# brick_serial_ble_MDBT40.net
KiCad netlist of a schematic drawn in EAGLE
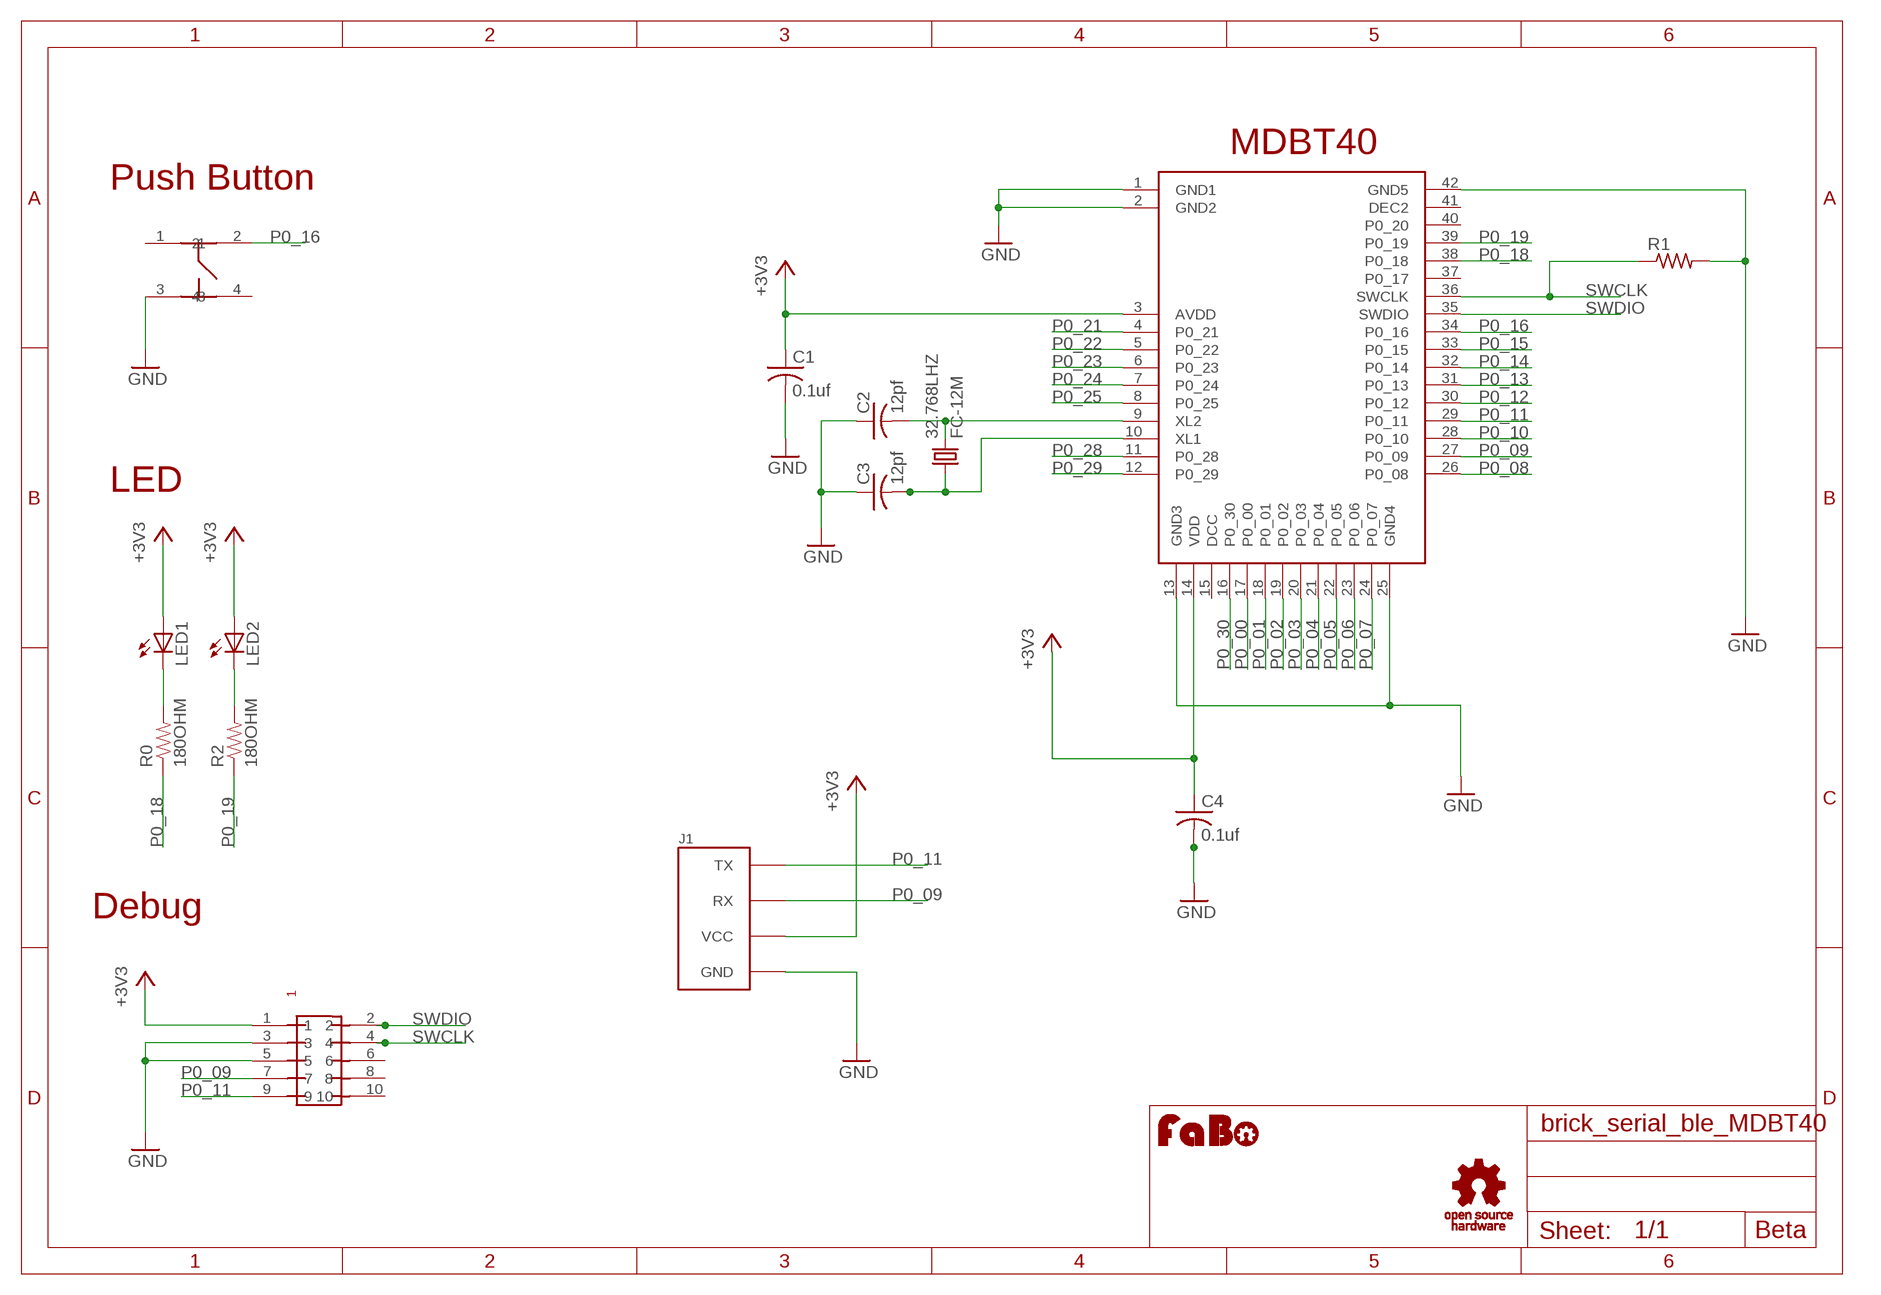
[diagram p0: schematic, sheet 1]

(export (version "E")
  (design (tool "Eeschema 10.0.6"))
  (components
    (comp (ref "32.768LHZ")
      (value "FC-12M")
      (footprint "eagle-import:FC-12M")
      (libsource (lib "eagle-import") (part "FC-12M"))
    )
    (comp (ref "C1")
      (value "0.1uf")
      (footprint "eagle-import:C0603")
      (libsource (lib "eagle-import") (part "C-USC0603"))
    )
    (comp (ref "C2")
      (value "12pf")
      (footprint "eagle-import:C0603")
      (libsource (lib "eagle-import") (part "C-USC0603"))
    )
    (comp (ref "C3")
      (value "12pf")
      (footprint "eagle-import:C0603")
      (libsource (lib "eagle-import") (part "C-USC0603"))
    )
    (comp (ref "C4")
      (value "0.1uf")
      (footprint "eagle-import:C0603")
      (libsource (lib "eagle-import") (part "C-USC0603"))
    )
    (comp (ref "J1")
      (value "BRICK_SERIAL")
      (footprint "eagle-import:BRICK_SERIAL")
      (libsource (lib "eagle-import") (part "BRICK_SERIAL"))
    )
    (comp (ref "LED1")
      (value "LEDCHIP-LED0603")
      (footprint "eagle-import:CHIP-LED0603")
      (libsource (lib "eagle-import") (part "LEDCHIP-LED0603"))
    )
    (comp (ref "LED2")
      (value "LEDCHIP-LED0603")
      (footprint "eagle-import:CHIP-LED0603")
      (libsource (lib "eagle-import") (part "LEDCHIP-LED0603"))
    )
    (comp (ref "R0")
      (value "180OHM")
      (footprint "eagle-import:0603-RES")
      (libsource (lib "eagle-import") (part "RESISTOR0603-RES"))
    )
    (comp (ref "R1")
      (value "R-US_R0603")
      (footprint "eagle-import:R0603")
      (libsource (lib "eagle-import") (part "R-US_R0603"))
    )
    (comp (ref "R2")
      (value "180OHM")
      (footprint "eagle-import:0603-RES")
      (libsource (lib "eagle-import") (part "RESISTOR0603-RES"))
    )
    (comp (ref "U$1")
      (value "RAYTAC-MDBT40")
      (footprint "eagle-import:RAYTAC-MDBT40")
      (libsource (lib "eagle-import") (part "RAYTAC-MDBT40"))
    )
    (comp (ref "U$2")
      (value "PIN-HEADER-SMT(1.27MM)2X5")
      (footprint "eagle-import:PIN-HEADER-SMT(1.27MM)2X5")
      (libsource (lib "eagle-import") (part "PIN-HEADER-SMT(1.27MM)2X5"))
    )
    (comp (ref "U$3")
      (value "LOGO_FABO-S")
      (footprint "eagle-import:LOGO_FABO_S")
      (libsource (lib "eagle-import") (part "LOGO_FABO-S"))
    )
    (comp (ref "U$4")
      (value "LOGO_OSHW_T-S")
      (footprint "eagle-import:LOGO_OSHW_T_S")
      (libsource (lib "eagle-import") (part "LOGO_OSHW_T-S"))
    )
    (comp (ref "U$5")
      (value "SWICTH-4P(KMR2)")
      (footprint "eagle-import:SWITCH-4P(KMR2)")
      (libsource (lib "eagle-import") (part "SWICTH-4P(KMR2)"))
    )
  )
  (nets
    (net (code "1") (name "+3V3") (class "Default")
      (node (ref "C1") (pin "1") (pinfunction "1_1") (pintype "passive"))
      (node (ref "C4") (pin "1") (pinfunction "1_1") (pintype "passive"))
      (node (ref "J1") (pin "VCC") (pinfunction "VCC_VCC") (pintype "bidirectional"))
      (node (ref "LED1") (pin "A") (pinfunction "A_A") (pintype "passive"))
      (node (ref "LED2") (pin "A") (pinfunction "A_A") (pintype "passive"))
      (node (ref "U$1") (pin "14") (pinfunction "VDD_14") (pintype "bidirectional"))
      (node (ref "U$1") (pin "3") (pinfunction "AVDD_3") (pintype "bidirectional"))
      (node (ref "U$2") (pin "1") (pinfunction "1_1") (pintype "bidirectional"))
    )
    (net (code "2") (name "/P0_00") (class "Default")
      (node (ref "U$1") (pin "17") (pinfunction "P0_00_17") (pintype "bidirectional"))
    )
    (net (code "3") (name "/P0_01") (class "Default")
      (node (ref "U$1") (pin "18") (pinfunction "P0_01_18") (pintype "bidirectional"))
    )
    (net (code "4") (name "/P0_02") (class "Default")
      (node (ref "U$1") (pin "19") (pinfunction "P0_02_19") (pintype "bidirectional"))
    )
    (net (code "5") (name "/P0_03") (class "Default")
      (node (ref "U$1") (pin "20") (pinfunction "P0_03_20") (pintype "bidirectional"))
    )
    (net (code "6") (name "/P0_04") (class "Default")
      (node (ref "U$1") (pin "21") (pinfunction "P0_04_21") (pintype "bidirectional"))
    )
    (net (code "7") (name "/P0_05") (class "Default")
      (node (ref "U$1") (pin "22") (pinfunction "P0_05_22") (pintype "bidirectional"))
    )
    (net (code "8") (name "/P0_06") (class "Default")
      (node (ref "U$1") (pin "23") (pinfunction "P0_06_23") (pintype "bidirectional"))
    )
    (net (code "9") (name "/P0_07") (class "Default")
      (node (ref "U$1") (pin "24") (pinfunction "P0_07_24") (pintype "bidirectional"))
    )
    (net (code "10") (name "/P0_08") (class "Default")
      (node (ref "U$1") (pin "26") (pinfunction "P0_08_26") (pintype "bidirectional"))
    )
    (net (code "11") (name "/P0_09") (class "Default")
      (node (ref "J1") (pin "RX") (pinfunction "RX_RX") (pintype "bidirectional"))
      (node (ref "U$1") (pin "27") (pinfunction "P0_09_27") (pintype "bidirectional"))
      (node (ref "U$2") (pin "7") (pinfunction "7_7") (pintype "bidirectional"))
    )
    (net (code "12") (name "/P0_10") (class "Default")
      (node (ref "U$1") (pin "28") (pinfunction "P0_10_28") (pintype "bidirectional"))
    )
    (net (code "13") (name "/P0_11") (class "Default")
      (node (ref "J1") (pin "TX") (pinfunction "TX_TX") (pintype "bidirectional"))
      (node (ref "U$1") (pin "29") (pinfunction "P0_11_29") (pintype "bidirectional"))
      (node (ref "U$2") (pin "9") (pinfunction "9_9") (pintype "bidirectional"))
    )
    (net (code "14") (name "/P0_12") (class "Default")
      (node (ref "U$1") (pin "30") (pinfunction "P0_12_30") (pintype "bidirectional"))
    )
    (net (code "15") (name "/P0_13") (class "Default")
      (node (ref "U$1") (pin "31") (pinfunction "P0_13_31") (pintype "bidirectional"))
    )
    (net (code "16") (name "/P0_14") (class "Default")
      (node (ref "U$1") (pin "32") (pinfunction "P0_14_32") (pintype "bidirectional"))
    )
    (net (code "17") (name "/P0_15") (class "Default")
      (node (ref "U$1") (pin "33") (pinfunction "P0_15_33") (pintype "bidirectional"))
    )
    (net (code "18") (name "/P0_16") (class "Default")
      (node (ref "U$1") (pin "34") (pinfunction "P0_16_34") (pintype "bidirectional"))
      (node (ref "U$5") (pin "2") (pinfunction "2_2") (pintype "bidirectional"))
    )
    (net (code "19") (name "/P0_18") (class "Default")
      (node (ref "R0") (pin "1") (pinfunction "1_1") (pintype "passive"))
      (node (ref "U$1") (pin "38") (pinfunction "P0_18_38") (pintype "bidirectional"))
    )
    (net (code "20") (name "/P0_19") (class "Default")
      (node (ref "R2") (pin "1") (pinfunction "1_1") (pintype "passive"))
      (node (ref "U$1") (pin "39") (pinfunction "P0_19_39") (pintype "bidirectional"))
    )
    (net (code "21") (name "/P0_21") (class "Default")
      (node (ref "U$1") (pin "4") (pinfunction "P0_21_4") (pintype "bidirectional"))
    )
    (net (code "22") (name "/P0_22") (class "Default")
      (node (ref "U$1") (pin "5") (pinfunction "P0_22_5") (pintype "bidirectional"))
    )
    (net (code "23") (name "/P0_23") (class "Default")
      (node (ref "U$1") (pin "6") (pinfunction "P0_23_6") (pintype "bidirectional"))
    )
    (net (code "24") (name "/P0_24") (class "Default")
      (node (ref "U$1") (pin "7") (pinfunction "P0_24_7") (pintype "bidirectional"))
    )
    (net (code "25") (name "/P0_25") (class "Default")
      (node (ref "U$1") (pin "8") (pinfunction "P0_25_8") (pintype "bidirectional"))
    )
    (net (code "26") (name "/P0_28") (class "Default")
      (node (ref "U$1") (pin "11") (pinfunction "P0_28_11") (pintype "bidirectional"))
    )
    (net (code "27") (name "/P0_29") (class "Default")
      (node (ref "U$1") (pin "12") (pinfunction "P0_29_12") (pintype "bidirectional"))
    )
    (net (code "28") (name "/P0_30") (class "Default")
      (node (ref "U$1") (pin "16") (pinfunction "P0_30_16") (pintype "bidirectional"))
    )
    (net (code "29") (name "/SWCLK") (class "Default")
      (node (ref "R1") (pin "1") (pinfunction "1_1") (pintype "passive"))
      (node (ref "U$1") (pin "36") (pinfunction "SWCLK_36") (pintype "bidirectional"))
      (node (ref "U$2") (pin "4") (pinfunction "4_4") (pintype "bidirectional"))
    )
    (net (code "30") (name "/SWDIO") (class "Default")
      (node (ref "U$1") (pin "35") (pinfunction "SWDIO_35") (pintype "bidirectional"))
      (node (ref "U$2") (pin "2") (pinfunction "2_2") (pintype "bidirectional"))
    )
    (net (code "31") (name "GND") (class "Default")
      (node (ref "C1") (pin "2") (pinfunction "2_2") (pintype "passive"))
      (node (ref "C2") (pin "1") (pinfunction "1_1") (pintype "passive"))
      (node (ref "C3") (pin "1") (pinfunction "1_1") (pintype "passive"))
      (node (ref "C4") (pin "2") (pinfunction "2_2") (pintype "passive"))
      (node (ref "J1") (pin "GND") (pinfunction "GND_GND") (pintype "bidirectional"))
      (node (ref "R1") (pin "2") (pinfunction "2_2") (pintype "passive"))
      (node (ref "U$1") (pin "1") (pinfunction "GND1_1") (pintype "bidirectional"))
      (node (ref "U$1") (pin "13") (pinfunction "GND3_13") (pintype "bidirectional"))
      (node (ref "U$1") (pin "2") (pinfunction "GND2_2") (pintype "bidirectional"))
      (node (ref "U$1") (pin "25") (pinfunction "GND4_25") (pintype "bidirectional"))
      (node (ref "U$1") (pin "42") (pinfunction "GND5_42") (pintype "bidirectional"))
      (node (ref "U$2") (pin "3") (pinfunction "3_3") (pintype "bidirectional"))
      (node (ref "U$2") (pin "5") (pinfunction "5_5") (pintype "bidirectional"))
      (node (ref "U$5") (pin "3") (pinfunction "3_3") (pintype "bidirectional"))
    )
    (net (code "32") (name "Net-(LED1-PadC)") (class "Default")
      (node (ref "LED1") (pin "C") (pinfunction "C_C") (pintype "passive"))
      (node (ref "R0") (pin "2") (pinfunction "2_2") (pintype "passive"))
    )
    (net (code "33") (name "Net-(LED2-PadC)") (class "Default")
      (node (ref "LED2") (pin "C") (pinfunction "C_C") (pintype "passive"))
      (node (ref "R2") (pin "2") (pinfunction "2_2") (pintype "passive"))
    )
    (net (code "34") (name "Net-(U$1-XL1)") (class "Default")
      (node (ref "32.768LHZ") (pin "1") (pinfunction "1_1") (pintype "passive"))
      (node (ref "C3") (pin "2") (pinfunction "2_2") (pintype "passive"))
      (node (ref "U$1") (pin "10") (pinfunction "XL1_10") (pintype "bidirectional"))
    )
    (net (code "35") (name "Net-(U$1-XL2)") (class "Default")
      (node (ref "32.768LHZ") (pin "2") (pinfunction "2_2") (pintype "passive"))
      (node (ref "C2") (pin "2") (pinfunction "2_2") (pintype "passive"))
      (node (ref "U$1") (pin "9") (pinfunction "XL2_9") (pintype "bidirectional"))
    )
    (net (code "36") (name "unconnected-(U$1-DCC-Pad15)") (class "Default")
      (node (ref "U$1") (pin "15") (pinfunction "DCC_15") (pintype "bidirectional"))
    )
    (net (code "37") (name "unconnected-(U$1-DEC2-Pad41)") (class "Default")
      (node (ref "U$1") (pin "41") (pinfunction "DEC2_41") (pintype "bidirectional"))
    )
    (net (code "38") (name "unconnected-(U$1-P0_17-Pad37)") (class "Default")
      (node (ref "U$1") (pin "37") (pinfunction "P0_17_37") (pintype "bidirectional"))
    )
    (net (code "39") (name "unconnected-(U$1-P0_20-Pad40)") (class "Default")
      (node (ref "U$1") (pin "40") (pinfunction "P0_20_40") (pintype "bidirectional"))
    )
    (net (code "40") (name "unconnected-(U$2-Pad6)") (class "Default")
      (node (ref "U$2") (pin "6") (pinfunction "6_6") (pintype "bidirectional"))
    )
    (net (code "41") (name "unconnected-(U$2-Pad8)") (class "Default")
      (node (ref "U$2") (pin "8") (pinfunction "8_8") (pintype "bidirectional"))
    )
    (net (code "42") (name "unconnected-(U$2-Pad10)") (class "Default")
      (node (ref "U$2") (pin "10") (pinfunction "10_10") (pintype "bidirectional"))
    )
    (net (code "43") (name "unconnected-(U$5-Pad1)") (class "Default")
      (node (ref "U$5") (pin "1") (pinfunction "1_1") (pintype "bidirectional"))
    )
    (net (code "44") (name "unconnected-(U$5-Pad4)") (class "Default")
      (node (ref "U$5") (pin "4") (pinfunction "4_4") (pintype "bidirectional"))
    )
  )
)
